# OBDII-Ist.net
KiCad netlist of a schematic drawn in Altium Designer
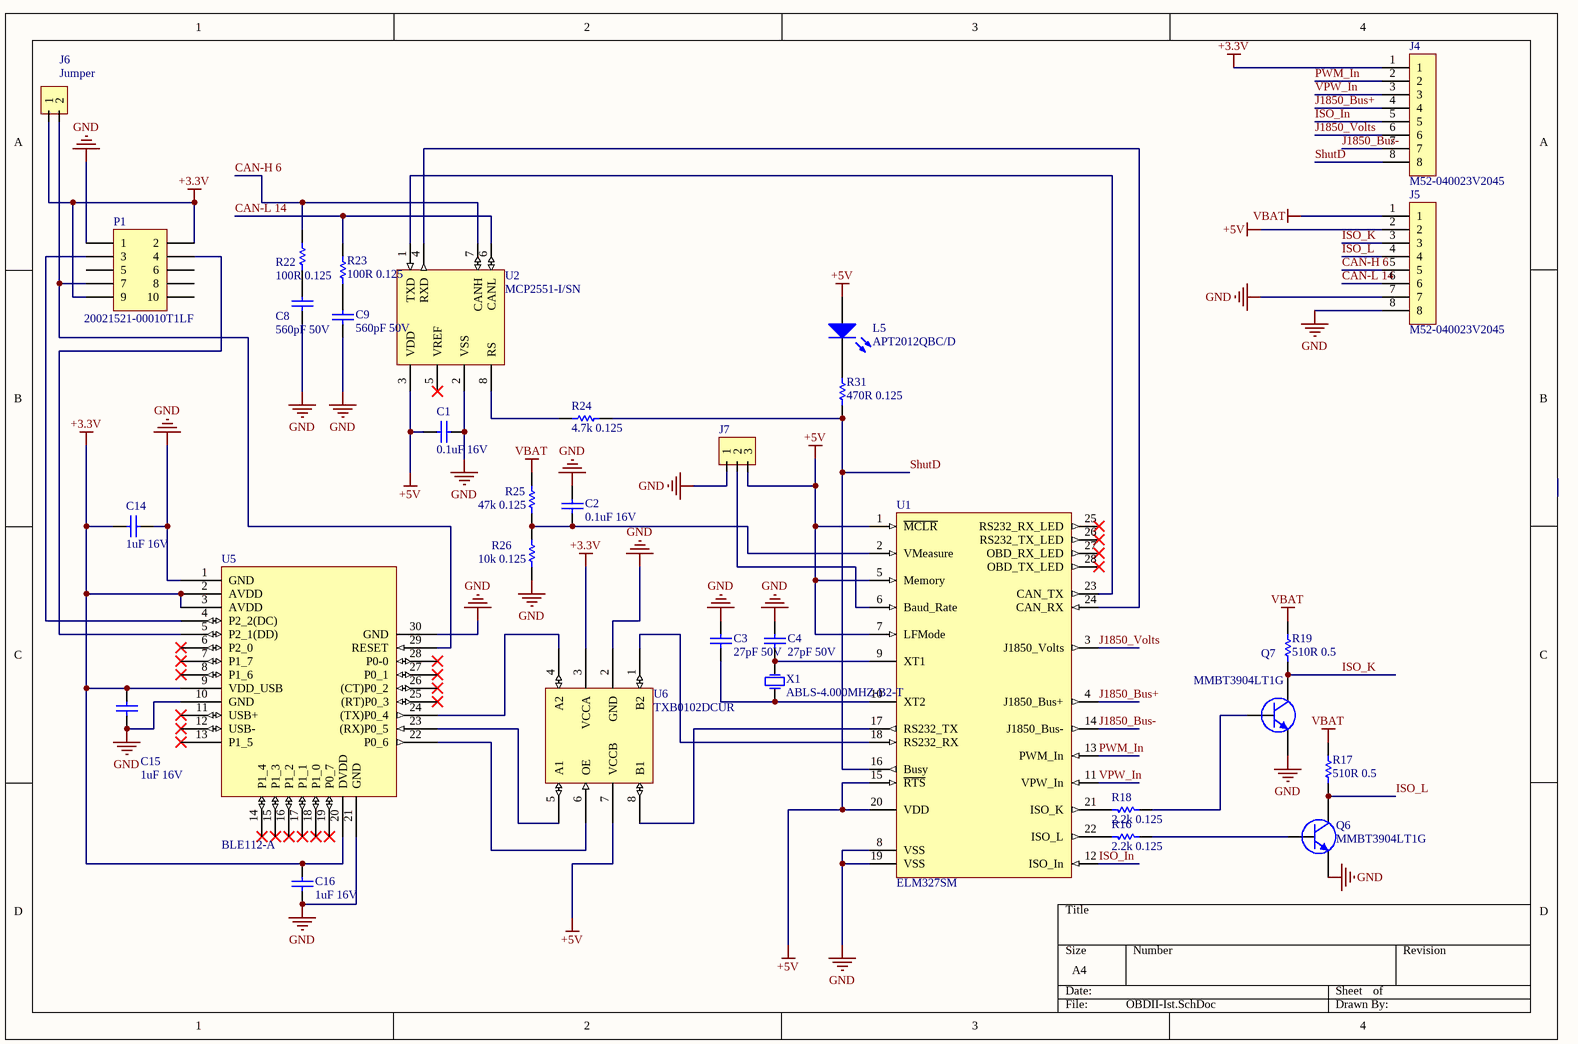
[diagram p0: OBDII-Ist.SchDoc]

(export (version "E")
  (design (tool "Eeschema 10.0.6"))
  (components
    (comp (ref "C1")
      (value "0.1uF 16V")
      (footprint "1608[0603]")
      (description "Surface-Mount Ceramic Multilayer Capacitor, 0.1uF, X5R, 10% Tolerance, 0603 Size, 16V")
      (fields (field (name "PUBLISHER") "Altium Limited"))
      (libsource (lib "OBDII-components") (part "GRM188R61C104KA01D"))
    )
    (comp (ref "C2")
      (value "0.1uF 16V")
      (footprint "1608[0603]")
      (description "Surface-Mount Ceramic Multilayer Capacitor, 0.1uF, X5R, 10% Tolerance, 0603 Size, 16V")
      (fields (field (name "PUBLISHER") "Altium Limited"))
      (libsource (lib "OBDII-components") (part "GRM188R61C104KA01D"))
    )
    (comp (ref "C3")
      (value "27pF 50V")
      (footprint "1608[0603]")
      (description "Surface-Mount Ceramic Multilayer Capacitor, 27pF, 5% Tolerance, 0603 Size, 50V")
      (fields (field (name "PUBLISHER") "Altium Limited"))
      (libsource (lib "OBDII-components") (part "CC0603JRNPO9BN270"))
    )
    (comp (ref "C4")
      (value "27pF 50V")
      (footprint "1608[0603]")
      (description "Surface-Mount Ceramic Multilayer Capacitor, 27pF, 5% Tolerance, 0603 Size, 50V")
      (fields (field (name "PUBLISHER") "Altium Limited"))
      (libsource (lib "OBDII-components") (part "CC0603JRNPO9BN270"))
    )
    (comp (ref "C8")
      (value "560pF 50V")
      (footprint "0402")
      (description "Surface-Mount Ceramic Multilayer Capacitor, 560pF, 5% Tolerance, 0402 Size, 50V")
      (fields (field (name "PUBLISHER") "Altium Limited"))
      (libsource (lib "OBDII-components") (part "C0402C561J5GACTU"))
    )
    (comp (ref "C9")
      (value "560pF 50V")
      (footprint "0402")
      (description "Surface-Mount Ceramic Multilayer Capacitor, 560pF, 5% Tolerance, 0402 Size, 50V")
      (fields (field (name "PUBLISHER") "Altium Limited"))
      (libsource (lib "OBDII-components") (part "C0402C561J5GACTU"))
    )
    (comp (ref "C14")
      (value "1uF 16V")
      (footprint "1608[0603]")
      (description "Surface-Mount Ceramic Multilayer Capacitor, 1uF, X7R, 10% Tolerance, 0603 Size, 16V")
      (libsource (lib "OBDII-components") (part "C1608X7R1C105K080AC"))
    )
    (comp (ref "C15")
      (value "1uF 16V")
      (footprint "1608[0603]")
      (description "Surface-Mount Ceramic Multilayer Capacitor, 1uF, X7R, 10% Tolerance, 0603 Size, 16V")
      (libsource (lib "OBDII-components") (part "C1608X7R1C105K080AC"))
    )
    (comp (ref "C16")
      (value "1uF 16V")
      (footprint "1608[0603]")
      (description "Surface-Mount Ceramic Multilayer Capacitor, 1uF, X7R, 10% Tolerance, 0603 Size, 16V")
      (libsource (lib "OBDII-components") (part "C1608X7R1C105K080AC"))
    )
    (comp (ref "J4")
      (value "M52-040023V2045")
      (footprint "M52-040023V2045_hols")
      (description "CONN HEADER .050\" 8POS PCB GOLD")
      (fields (field (name "MANUFACTURER") "Harwin"))
      (libsource (lib "OBDII-components") (part "M52-040023V2045_hols"))
    )
    (comp (ref "J5")
      (value "M52-040023V2045")
      (footprint "M52-040023V2045_hols")
      (description "CONN HEADER .050\" 8POS PCB GOLD")
      (fields (field (name "MANUFACTURER") "Harwin"))
      (libsource (lib "OBDII-components") (part "M52-040023V2045_hols"))
    )
    (comp (ref "J6")
      (value "Jumper")
      (footprint "Jumper")
      (description "Solder Jumper")
      (libsource (lib "OBDII-components") (part "Jumper"))
    )
    (comp (ref "J7")
      (value "Solder Junper Switcher")
      (footprint "Jumper-3")
      (description "Solder Jumper Switcher")
      (libsource (lib "OBDII-components") (part "Jumper-3"))
    )
    (comp (ref "L5")
      (value "APT2012QBC/D")
      (footprint "LED-0805")
      (description "Typical BLUE SiC LED")
      (libsource (lib "OBDII-components") (part "APT2012QBC/D"))
    )
    (comp (ref "P1")
      (value "20021521-00010T1LF")
      (footprint "20021521-00010T1LF")
      (description "Header, 5-Pin, Dual row,SMT SHOULDED")
      (fields (field (name "TYPE") "20021521-00010T1LF") (field (name "PUBLISHER") "Altium Limited"))
      (libsource (lib "OBDII-components") (part "20021521-00010T1LF"))
    )
    (comp (ref "Q6")
      (value "MMBT3904LT1G")
      (footprint "SOT23")
      (description "NPN 3904 General Purpose Amplifier")
      (fields
        (field (name "MANUFACTURER") "ON Semiconductor")
        (field (name "PUBLISHER") "Vanteon")
        (field (name "APPROVED") "Yes by Implemenation")
      )
      (libsource (lib "OBDII-components") (part "MMBT3904LT1G"))
    )
    (comp (ref "Q7")
      (value "MMBT3904LT1G")
      (footprint "SOT23")
      (description "NPN 3904 General Purpose Amplifier")
      (fields
        (field (name "MANUFACTURER") "ON Semiconductor")
        (field (name "PUBLISHER") "Vanteon")
        (field (name "APPROVED") "Yes by Implemenation")
      )
      (libsource (lib "OBDII-components") (part "MMBT3904LT1G"))
    )
    (comp (ref "R16")
      (value "2.2k 0.125")
      (footprint "ERA-0805")
      (description "Rectangular Thick Film Chip Resistor, 2.2 kOhm, 0.1% Tolerance, 0805 Size, 0.125 W")
      (libsource (lib "OBDII-components") (part "ERA-6AEB222V"))
    )
    (comp (ref "R17")
      (value "510R 0.5")
      (footprint "ERJ-1210")
      (description "Rectangular Thick Film Chip Resistor, 510 Ohm, 1% Tolerance, 1210 Size, 0.5 W")
      (libsource (lib "OBDII-components") (part "ERJ-14NF5100U"))
    )
    (comp (ref "R18")
      (value "2.2k 0.125")
      (footprint "ERA-0805")
      (description "Rectangular Thick Film Chip Resistor, 2.2 kOhm, 0.1% Tolerance, 0805 Size, 0.125 W")
      (libsource (lib "OBDII-components") (part "ERA-6AEB222V"))
    )
    (comp (ref "R19")
      (value "510R 0.5")
      (footprint "ERJ-1210")
      (description "Rectangular Thick Film Chip Resistor, 510 Ohm, 1% Tolerance, 1210 Size, 0.5 W")
      (libsource (lib "OBDII-components") (part "ERJ-14NF5100U"))
    )
    (comp (ref "R22")
      (value "100R 0.125")
      (footprint "ERA-0805")
      (description "Rectangular Thick Film Chip Resistor, 100 Ohm, 0.1% Tolerance, 0805 Size, 0.125 W")
      (libsource (lib "OBDII-components") (part "ERA-6AEB101V"))
    )
    (comp (ref "R23")
      (value "100R 0.125")
      (footprint "ERA-0805")
      (description "Rectangular Thick Film Chip Resistor, 100 Ohm, 0.1% Tolerance, 0805 Size, 0.125 W")
      (libsource (lib "OBDII-components") (part "ERA-6AEB101V"))
    )
    (comp (ref "R24")
      (value "4.7k 0.125")
      (footprint "ERA-0805")
      (description "Rectangular Thick Film Chip Resistor, 4.7 kOhm, 0.1% Tolerance, 0805 Size, 0.125 W")
      (libsource (lib "OBDII-components") (part "ERA-6AEB472V"))
    )
    (comp (ref "R25")
      (value "47k 0.125")
      (footprint "ERA-0805")
      (description "Rectangular Thick Film Chip Resistor, 47 kOhm, 0.1% Tolerance, 0805 Size, 0.125 W")
      (libsource (lib "OBDII-components") (part "ERA-6AEB473V"))
    )
    (comp (ref "R26")
      (value "10k 0.125")
      (footprint "ERA-0805")
      (description "Rectangular Thick Film Chip Resistor, 10 kOhm, 0.1% Tolerance, 0805 Size, 0.125 W")
      (libsource (lib "OBDII-components") (part "ERA-6AEB103V"))
    )
    (comp (ref "R31")
      (value "470R 0.125")
      (footprint "ERA-0805")
      (description "Rectangular Thick Film Chip Resistor, 470 Ohm, 0.1% Tolerance, 0805 Size, 0.125 W")
      (libsource (lib "OBDII-components") (part "ERA-6AEB471V"))
    )
    (comp (ref "U1")
      (value "ELM327SM")
      (footprint "SOIC-28N")
      (description "OBDII Interpreter IC")
      (fields (field (name "MANUFACTURER") "Elm Electronics"))
      (libsource (lib "OBDII-components") (part "ELM327_SOIC"))
    )
    (comp (ref "U2")
      (value "MCP2551-I/SN")
      (footprint "SOIC8N")
      (description "IC TRANSCEIVER CAN HI-SPD 8-SOIC")
      (fields (field (name "MANUFACTURER") "Microchip Technology"))
      (libsource (lib "OBDII-components") (part "MCP2551-I/SN"))
    )
    (comp (ref "U5")
      (value "BLE112-A")
      (footprint "BLE112-A - II")
      (description "BLE112 Bluetooth Smart Module")
      (libsource (lib "OBDII-components") (part "BLE112-A"))
    )
    (comp (ref "U6")
      (value "TXB0102DCUR")
      (footprint "TXB0102DCUR")
      (description "2-Bit Bidirectional Voltage-Level Translator with Auto Direction Sensing and +/-15-kV ESD Protect")
      (libsource (lib "OBDII-components") (part "TXB0102DCUR"))
    )
    (comp (ref "X1")
      (value "ABLS-4.000MHZ-B2-T")
      (footprint "HC-49/US")
      (description "CRYSTAL 4.000 MHZ 18PF SMD")
      (fields (field (name "MANUFACTURER") "Abracon"))
      (libsource (lib "OBDII-components") (part "ABLS-4.000MHZ-B2-T"))
    )
  )
  (nets
    (net (code "1") (name "+3.3V") (class "Default")
      (node (ref "C14") (pin "1") (pinfunction "1_1") (pintype "passive"))
      (node (ref "C15") (pin "2") (pinfunction "2_2") (pintype "passive"))
      (node (ref "C16") (pin "2") (pinfunction "2_2") (pintype "passive"))
      (node (ref "J4") (pin "1") (pinfunction "1_1") (pintype "passive"))
      (node (ref "J6") (pin "1") (pinfunction "1_1") (pintype "passive"))
      (node (ref "P1") (pin "2") (pinfunction "2_2") (pintype "passive"))
      (node (ref "P1") (pin "9") (pinfunction "9_9") (pintype "passive"))
      (node (ref "U5") (pin "2") (pinfunction "AVDD_2") (pintype "power_in"))
      (node (ref "U5") (pin "20") (pinfunction "DVDD_20") (pintype "power_in"))
      (node (ref "U5") (pin "3") (pinfunction "AVDD_3") (pintype "power_in"))
      (node (ref "U5") (pin "9") (pinfunction "VDD_USB_9") (pintype "power_in"))
      (node (ref "U6") (pin "3") (pinfunction "VCCA_3") (pintype "power_in"))
    )
    (net (code "2") (name "+5V") (class "Default")
      (node (ref "C1") (pin "1") (pinfunction "1_1") (pintype "passive"))
      (node (ref "J5") (pin "2") (pinfunction "2_2") (pintype "passive"))
      (node (ref "J7") (pin "3") (pinfunction "3_3") (pintype "passive"))
      (node (ref "L5") (pin "1") (pinfunction "A_1") (pintype "passive"))
      (node (ref "U1") (pin "1") (pinfunction "~{MCLR}_1") (pintype "input"))
      (node (ref "U1") (pin "15") (pinfunction "~{RTS}_15") (pintype "input"))
      (node (ref "U1") (pin "20") (pinfunction "VDD_20") (pintype "power_in"))
      (node (ref "U1") (pin "5") (pinfunction "Memory_5") (pintype "input"))
      (node (ref "U1") (pin "7") (pinfunction "LFMode_7") (pintype "input"))
      (node (ref "U2") (pin "3") (pinfunction "VDD_3") (pintype "power_in"))
      (node (ref "U6") (pin "7") (pinfunction "VCCB_7") (pintype "power_in"))
    )
    (net (code "3") (name "/CAN-H 6") (class "Default")
      (node (ref "J5") (pin "5") (pinfunction "5_5") (pintype "passive"))
      (node (ref "R22") (pin "2") (pinfunction "2_2") (pintype "passive"))
      (node (ref "U2") (pin "7") (pinfunction "CANH_7") (pintype "bidirectional"))
    )
    (net (code "4") (name "/CAN-L 14") (class "Default")
      (node (ref "J5") (pin "6") (pinfunction "6_6") (pintype "passive"))
      (node (ref "R23") (pin "2") (pinfunction "2_2") (pintype "passive"))
      (node (ref "U2") (pin "6") (pinfunction "CANL_6") (pintype "bidirectional"))
    )
    (net (code "5") (name "/ISO_In") (class "Default")
      (node (ref "J4") (pin "5") (pinfunction "5_5") (pintype "passive"))
      (node (ref "U1") (pin "12") (pinfunction "ISO_In_12") (pintype "input"))
    )
    (net (code "6") (name "/ISO_K") (class "Default")
      (node (ref "J5") (pin "3") (pinfunction "3_3") (pintype "passive"))
      (node (ref "Q7") (pin "3") (pinfunction "C_3") (pintype "passive"))
      (node (ref "R19") (pin "1") (pinfunction "1_1") (pintype "passive"))
    )
    (net (code "7") (name "/ISO_L") (class "Default")
      (node (ref "J5") (pin "4") (pinfunction "4_4") (pintype "passive"))
      (node (ref "Q6") (pin "3") (pinfunction "C_3") (pintype "passive"))
      (node (ref "R17") (pin "1") (pinfunction "1_1") (pintype "passive"))
    )
    (net (code "8") (name "/J1850_Bus+") (class "Default")
      (node (ref "J4") (pin "4") (pinfunction "4_4") (pintype "passive"))
      (node (ref "U1") (pin "4") (pinfunction "J1850_Bus+_4") (pintype "output"))
    )
    (net (code "9") (name "/J1850_Bus-") (class "Default")
      (node (ref "J4") (pin "7") (pinfunction "7_7") (pintype "passive"))
      (node (ref "U1") (pin "14") (pinfunction "J1850_Bus-_14") (pintype "output"))
    )
    (net (code "10") (name "/J1850_Volts") (class "Default")
      (node (ref "J4") (pin "6") (pinfunction "6_6") (pintype "passive"))
      (node (ref "U1") (pin "3") (pinfunction "J1850_Volts_3") (pintype "output"))
    )
    (net (code "11") (name "/PWM_In") (class "Default")
      (node (ref "J4") (pin "2") (pinfunction "2_2") (pintype "passive"))
      (node (ref "U1") (pin "13") (pinfunction "PWM_In_13") (pintype "input"))
    )
    (net (code "12") (name "/ShutD") (class "Default")
      (node (ref "J4") (pin "8") (pinfunction "8_8") (pintype "passive"))
      (node (ref "R24") (pin "2") (pinfunction "2_2") (pintype "passive"))
      (node (ref "R31") (pin "1") (pinfunction "1_1") (pintype "passive"))
      (node (ref "U1") (pin "16") (pinfunction "Busy_16") (pintype "output"))
    )
    (net (code "13") (name "/VPW_In") (class "Default")
      (node (ref "J4") (pin "3") (pinfunction "3_3") (pintype "passive"))
      (node (ref "U1") (pin "11") (pinfunction "VPW_In_11") (pintype "input"))
    )
    (net (code "14") (name "GND") (class "Default")
      (node (ref "C1") (pin "2") (pinfunction "2_2") (pintype "passive"))
      (node (ref "C14") (pin "2") (pinfunction "2_2") (pintype "passive"))
      (node (ref "C15") (pin "1") (pinfunction "1_1") (pintype "passive"))
      (node (ref "C16") (pin "1") (pinfunction "1_1") (pintype "passive"))
      (node (ref "C2") (pin "2") (pinfunction "2_2") (pintype "passive"))
      (node (ref "C3") (pin "2") (pinfunction "2_2") (pintype "passive"))
      (node (ref "C4") (pin "2") (pinfunction "2_2") (pintype "passive"))
      (node (ref "C8") (pin "1") (pinfunction "1_1") (pintype "passive"))
      (node (ref "C9") (pin "1") (pinfunction "1_1") (pintype "passive"))
      (node (ref "J5") (pin "7") (pinfunction "7_7") (pintype "passive"))
      (node (ref "J5") (pin "8") (pinfunction "8_8") (pintype "passive"))
      (node (ref "J7") (pin "1") (pinfunction "1_1") (pintype "passive"))
      (node (ref "P1") (pin "1") (pinfunction "1_1") (pintype "passive"))
      (node (ref "Q6") (pin "2") (pinfunction "E_2") (pintype "passive"))
      (node (ref "Q7") (pin "2") (pinfunction "E_2") (pintype "passive"))
      (node (ref "R26") (pin "1") (pinfunction "1_1") (pintype "passive"))
      (node (ref "U1") (pin "19") (pinfunction "VSS_19") (pintype "power_in"))
      (node (ref "U1") (pin "8") (pinfunction "VSS_8") (pintype "power_in"))
      (node (ref "U2") (pin "2") (pinfunction "VSS_2") (pintype "power_in"))
      (node (ref "U5") (pin "1") (pinfunction "GND_1") (pintype "power_in"))
      (node (ref "U5") (pin "10") (pinfunction "GND_10") (pintype "passive"))
      (node (ref "U5") (pin "21") (pinfunction "GND_21") (pintype "power_in"))
      (node (ref "U5") (pin "30") (pinfunction "GND_30") (pintype "power_in"))
      (node (ref "U6") (pin "2") (pinfunction "GND_2") (pintype "power_in"))
    )
    (net (code "15") (name "Net-(C8-Pad2)") (class "Default")
      (node (ref "C8") (pin "2") (pinfunction "2_2") (pintype "passive"))
      (node (ref "R22") (pin "1") (pinfunction "1_1") (pintype "passive"))
    )
    (net (code "16") (name "Net-(C9-Pad2)") (class "Default")
      (node (ref "C9") (pin "2") (pinfunction "2_2") (pintype "passive"))
      (node (ref "R23") (pin "1") (pinfunction "1_1") (pintype "passive"))
    )
    (net (code "17") (name "Net-(L5-K)") (class "Default")
      (node (ref "L5") (pin "2") (pinfunction "K_2") (pintype "passive"))
      (node (ref "R31") (pin "2") (pinfunction "2_2") (pintype "passive"))
    )
    (net (code "18") (name "Net-(Q6-B)") (class "Default")
      (node (ref "Q6") (pin "1") (pinfunction "B_1") (pintype "passive"))
      (node (ref "R16") (pin "1") (pinfunction "1_1") (pintype "passive"))
    )
    (net (code "19") (name "Net-(Q7-B)") (class "Default")
      (node (ref "Q7") (pin "1") (pinfunction "B_1") (pintype "passive"))
      (node (ref "R18") (pin "1") (pinfunction "1_1") (pintype "passive"))
    )
    (net (code "20") (name "Net-(U1-Baud_Rate)") (class "Default")
      (node (ref "J7") (pin "2") (pinfunction "2_2") (pintype "passive"))
      (node (ref "U1") (pin "6") (pinfunction "Baud_Rate_6") (pintype "input"))
    )
    (net (code "21") (name "Net-(U1-CAN_RX)") (class "Default")
      (node (ref "U1") (pin "24") (pinfunction "CAN_RX_24") (pintype "input"))
      (node (ref "U2") (pin "4") (pinfunction "RXD_4") (pintype "output"))
    )
    (net (code "22") (name "Net-(U1-CAN_TX)") (class "Default")
      (node (ref "U1") (pin "23") (pinfunction "CAN_TX_23") (pintype "output"))
      (node (ref "U2") (pin "1") (pinfunction "TXD_1") (pintype "input"))
    )
    (net (code "23") (name "Net-(U1-ISO_K)") (class "Default")
      (node (ref "R18") (pin "2") (pinfunction "2_2") (pintype "passive"))
      (node (ref "U1") (pin "21") (pinfunction "ISO_K_21") (pintype "output"))
    )
    (net (code "24") (name "Net-(U1-ISO_L)") (class "Default")
      (node (ref "R16") (pin "2") (pinfunction "2_2") (pintype "passive"))
      (node (ref "U1") (pin "22") (pinfunction "ISO_L_22") (pintype "output"))
    )
    (net (code "25") (name "Net-(U1-RS232_RX)") (class "Default")
      (node (ref "U1") (pin "18") (pinfunction "RS232_RX_18") (pintype "input"))
      (node (ref "U6") (pin "1") (pinfunction "B2_1") (pintype "bidirectional"))
    )
    (net (code "26") (name "Net-(U1-RS232_TX)") (class "Default")
      (node (ref "U1") (pin "17") (pinfunction "RS232_TX_17") (pintype "output"))
      (node (ref "U6") (pin "8") (pinfunction "B1_8") (pintype "bidirectional"))
    )
    (net (code "27") (name "Net-(U1-VMeasure)") (class "Default")
      (node (ref "C2") (pin "1") (pinfunction "1_1") (pintype "passive"))
      (node (ref "R25") (pin "1") (pinfunction "1_1") (pintype "passive"))
      (node (ref "R26") (pin "2") (pinfunction "2_2") (pintype "passive"))
      (node (ref "U1") (pin "2") (pinfunction "VMeasure_2") (pintype "input"))
    )
    (net (code "28") (name "Net-(U1-XT1)") (class "Default")
      (node (ref "C4") (pin "1") (pinfunction "1_1") (pintype "passive"))
      (node (ref "U1") (pin "9") (pinfunction "XT1_9") (pintype "passive"))
      (node (ref "X1") (pin "2") (pinfunction "OSC2_2") (pintype "passive"))
    )
    (net (code "29") (name "Net-(U1-XT2)") (class "Default")
      (node (ref "C3") (pin "1") (pinfunction "1_1") (pintype "passive"))
      (node (ref "U1") (pin "10") (pinfunction "XT2_10") (pintype "passive"))
      (node (ref "X1") (pin "1") (pinfunction "OSC1_1") (pintype "passive"))
    )
    (net (code "30") (name "Net-(U2-RS)") (class "Default")
      (node (ref "R24") (pin "1") (pinfunction "1_1") (pintype "passive"))
      (node (ref "U2") (pin "8") (pinfunction "RS_8") (pintype "passive"))
    )
    (net (code "31") (name "Net-(U5-(RX)P0_5)") (class "Default")
      (node (ref "U5") (pin "23") (pinfunction "(RX)P0_5_23") (pintype "input"))
      (node (ref "U6") (pin "5") (pinfunction "A1_5") (pintype "bidirectional"))
    )
    (net (code "32") (name "Net-(U5-(TX)P0_4)") (class "Default")
      (node (ref "U5") (pin "24") (pinfunction "(TX)P0_4_24") (pintype "output"))
      (node (ref "U6") (pin "4") (pinfunction "A2_4") (pintype "bidirectional"))
    )
    (net (code "33") (name "Net-(U5-P0_6)") (class "Default")
      (node (ref "U5") (pin "22") (pinfunction "P0_6_22") (pintype "output"))
      (node (ref "U6") (pin "6") (pinfunction "OE_6") (pintype "input"))
    )
    (net (code "34") (name "Net-(U5-P2_1(DD))") (class "Default")
      (node (ref "P1") (pin "4") (pinfunction "4_4") (pintype "passive"))
      (node (ref "U5") (pin "5") (pinfunction "P2_1(DD)_5") (pintype "bidirectional"))
    )
    (net (code "35") (name "Net-(U5-P2_2(DC))") (class "Default")
      (node (ref "P1") (pin "3") (pinfunction "3_3") (pintype "passive"))
      (node (ref "U5") (pin "4") (pinfunction "P2_2(DC)_4") (pintype "bidirectional"))
    )
    (net (code "36") (name "Net-(U5-RESET)") (class "Default")
      (node (ref "J6") (pin "2") (pinfunction "2_2") (pintype "passive"))
      (node (ref "P1") (pin "7") (pinfunction "7_7") (pintype "passive"))
      (node (ref "U5") (pin "29") (pinfunction "RESET_29") (pintype "input"))
    )
    (net (code "37") (name "VBAT") (class "Default")
      (node (ref "J5") (pin "1") (pinfunction "1_1") (pintype "passive"))
      (node (ref "R17") (pin "2") (pinfunction "2_2") (pintype "passive"))
      (node (ref "R19") (pin "2") (pinfunction "2_2") (pintype "passive"))
      (node (ref "R25") (pin "2") (pinfunction "2_2") (pintype "passive"))
    )
    (net (code "38") (name "unconnected-(P1-Pad5)") (class "Default")
      (node (ref "P1") (pin "5") (pinfunction "5_5") (pintype "passive"))
    )
    (net (code "39") (name "unconnected-(P1-Pad6)") (class "Default")
      (node (ref "P1") (pin "6") (pinfunction "6_6") (pintype "passive"))
    )
    (net (code "40") (name "unconnected-(P1-Pad8)") (class "Default")
      (node (ref "P1") (pin "8") (pinfunction "8_8") (pintype "passive"))
    )
    (net (code "41") (name "unconnected-(P1-Pad10)") (class "Default")
      (node (ref "P1") (pin "10") (pinfunction "10_10") (pintype "passive"))
    )
    (net (code "42") (name "unconnected-(U1-OBD_RX_LED-Pad27)") (class "Default")
      (node (ref "U1") (pin "27") (pinfunction "OBD_RX_LED_27") (pintype "output+no_connect"))
    )
    (net (code "43") (name "unconnected-(U1-OBD_TX_LED-Pad28)") (class "Default")
      (node (ref "U1") (pin "28") (pinfunction "OBD_TX_LED_28") (pintype "output+no_connect"))
    )
    (net (code "44") (name "unconnected-(U1-RS232_RX_LED-Pad25)") (class "Default")
      (node (ref "U1") (pin "25") (pinfunction "RS232_RX_LED_25") (pintype "output+no_connect"))
    )
    (net (code "45") (name "unconnected-(U1-RS232_TX_LED-Pad26)") (class "Default")
      (node (ref "U1") (pin "26") (pinfunction "RS232_TX_LED_26") (pintype "output+no_connect"))
    )
    (net (code "46") (name "unconnected-(U2-VREF-Pad5)") (class "Default")
      (node (ref "U2") (pin "5") (pinfunction "VREF_5") (pintype "passive+no_connect"))
    )
    (net (code "47") (name "unconnected-(U5-(CT)P0_2-Pad26)") (class "Default")
      (node (ref "U5") (pin "26") (pinfunction "(CT)P0_2_26") (pintype "bidirectional+no_connect"))
    )
    (net (code "48") (name "unconnected-(U5-(RT)P0_3-Pad25)") (class "Default")
      (node (ref "U5") (pin "25") (pinfunction "(RT)P0_3_25") (pintype "bidirectional+no_connect"))
    )
    (net (code "49") (name "unconnected-(U5-P0-0-Pad28)") (class "Default")
      (node (ref "U5") (pin "28") (pinfunction "P0-0_28") (pintype "bidirectional+no_connect"))
    )
    (net (code "50") (name "unconnected-(U5-P0_1-Pad27)") (class "Default")
      (node (ref "U5") (pin "27") (pinfunction "P0_1_27") (pintype "bidirectional+no_connect"))
    )
    (net (code "51") (name "unconnected-(U5-P0_7-Pad19)") (class "Default")
      (node (ref "U5") (pin "19") (pinfunction "P0_7_19") (pintype "bidirectional+no_connect"))
    )
    (net (code "52") (name "unconnected-(U5-P1_0-Pad18)") (class "Default")
      (node (ref "U5") (pin "18") (pinfunction "P1_0_18") (pintype "bidirectional+no_connect"))
    )
    (net (code "53") (name "unconnected-(U5-P1_1-Pad17)") (class "Default")
      (node (ref "U5") (pin "17") (pinfunction "P1_1_17") (pintype "bidirectional+no_connect"))
    )
    (net (code "54") (name "unconnected-(U5-P1_2-Pad16)") (class "Default")
      (node (ref "U5") (pin "16") (pinfunction "P1_2_16") (pintype "bidirectional+no_connect"))
    )
    (net (code "55") (name "unconnected-(U5-P1_3-Pad15)") (class "Default")
      (node (ref "U5") (pin "15") (pinfunction "P1_3_15") (pintype "bidirectional+no_connect"))
    )
    (net (code "56") (name "unconnected-(U5-P1_4-Pad14)") (class "Default")
      (node (ref "U5") (pin "14") (pinfunction "P1_4_14") (pintype "bidirectional+no_connect"))
    )
    (net (code "57") (name "unconnected-(U5-P1_5-Pad13)") (class "Default")
      (node (ref "U5") (pin "13") (pinfunction "P1_5_13") (pintype "passive+no_connect"))
    )
    (net (code "58") (name "unconnected-(U5-P1_6-Pad8)") (class "Default")
      (node (ref "U5") (pin "8") (pinfunction "P1_6_8") (pintype "bidirectional+no_connect"))
    )
    (net (code "59") (name "unconnected-(U5-P1_7-Pad7)") (class "Default")
      (node (ref "U5") (pin "7") (pinfunction "P1_7_7") (pintype "bidirectional+no_connect"))
    )
    (net (code "60") (name "unconnected-(U5-P2_0-Pad6)") (class "Default")
      (node (ref "U5") (pin "6") (pinfunction "P2_0_6") (pintype "bidirectional+no_connect"))
    )
    (net (code "61") (name "unconnected-(U5-USB+-Pad11)") (class "Default")
      (node (ref "U5") (pin "11") (pinfunction "USB+_11") (pintype "bidirectional+no_connect"))
    )
    (net (code "62") (name "unconnected-(U5-USB--Pad12)") (class "Default")
      (node (ref "U5") (pin "12") (pinfunction "USB-_12") (pintype "bidirectional+no_connect"))
    )
  )
)
